# PID__v2.net
KiCad netlist of a schematic drawn in Altium Designer
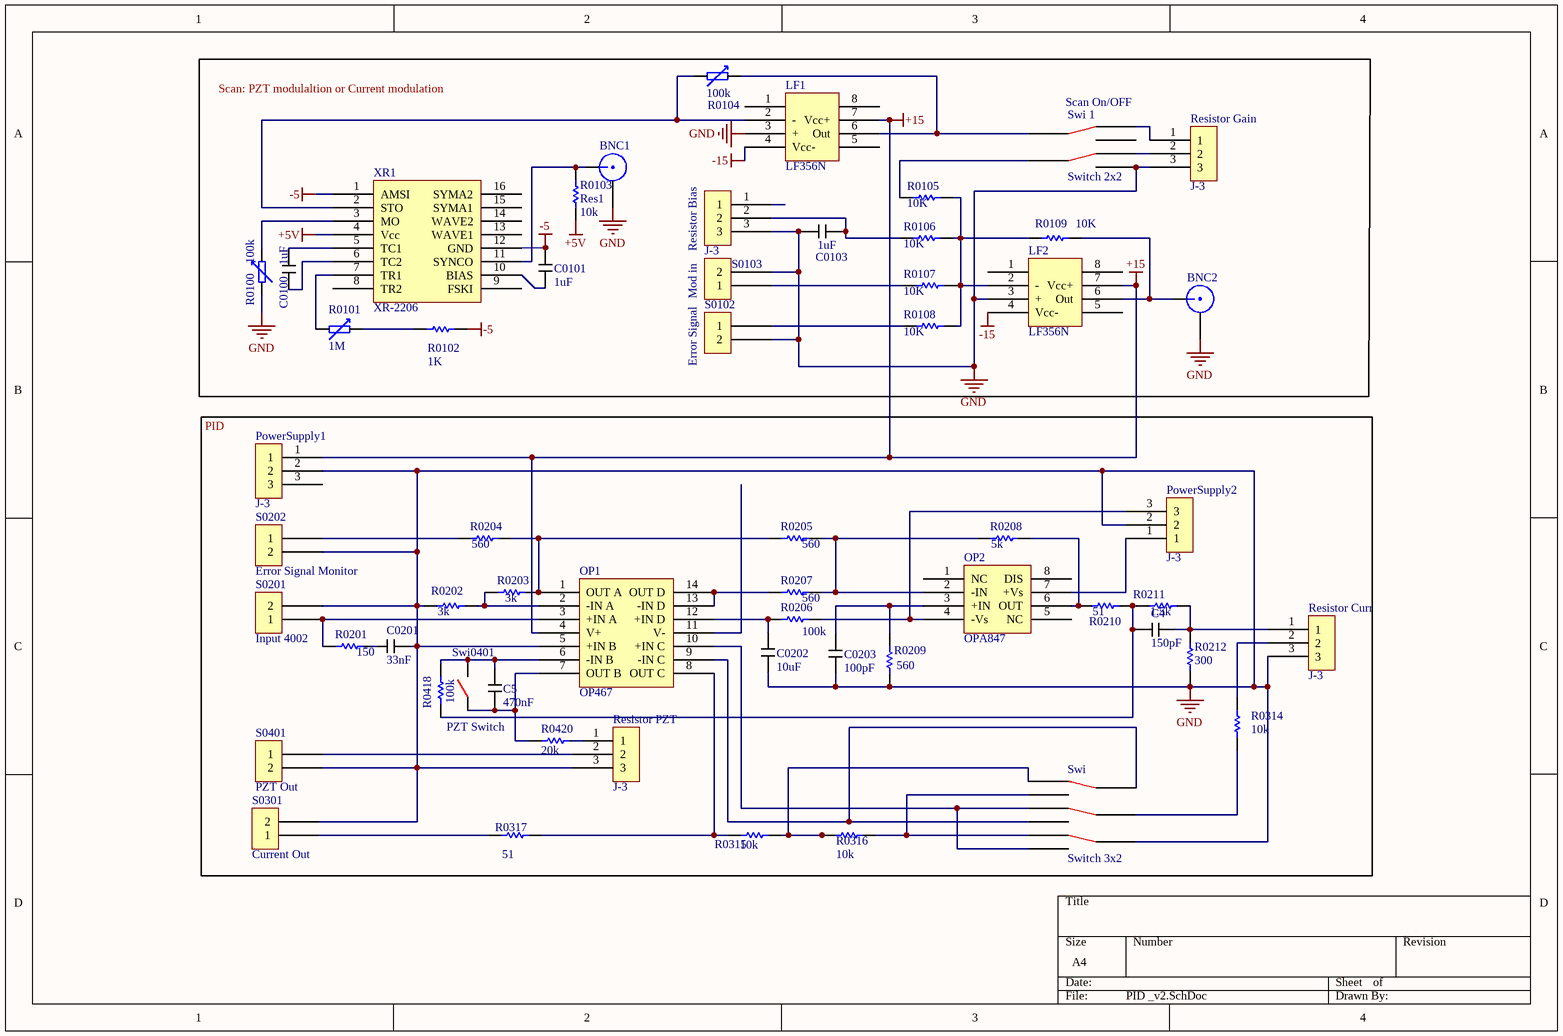
[diagram p0: PID _v2.SchDoc]

(export (version "E")
  (design (tool "Eeschema 10.0.6"))
  (components
    (comp (ref "BNC1") (value "BNC") (footprint "BNC-KE") (libsource (lib "Schlib1") (part "BNC")))
    (comp (ref "BNC2") (value "BNC") (footprint "BNC-KE") (libsource (lib "Schlib1") (part "BNC")))
    (comp (ref "C4") (value "150pF") (footprint "Capacitor") (libsource (lib "Schlib1") (part "Cap")))
    (comp (ref "C5") (value "470nF") (footprint "Capacitor") (libsource (lib "Schlib1") (part "Cap")))
    (comp (ref "C0100") (value "1uF") (footprint "Capacitor") (libsource (lib "Schlib1") (part "Cap")))
    (comp (ref "C0101") (value "1uF") (footprint "Capacitor") (libsource (lib "Schlib1") (part "Cap")))
    (comp (ref "C0103") (value "1uF") (footprint "Capacitor") (libsource (lib "Schlib1") (part "Cap")))
    (comp (ref "C0201") (value "33nF") (footprint "Capacitor") (libsource (lib "Schlib1") (part "Cap")))
    (comp (ref "C0202") (value "10uF") (footprint "Capacitor") (libsource (lib "Schlib1") (part "Cap")))
    (comp (ref "C0203") (value "100pF") (footprint "Capacitor") (libsource (lib "Schlib1") (part "Cap")))
    (comp (ref "LF1") (value "LF356N") (footprint "DIP8") (libsource (lib "Schlib1") (part "LF356N")))
    (comp (ref "LF2") (value "LF356N") (footprint "DIP8") (libsource (lib "Schlib1") (part "LF356N")))
    (comp (ref "OP1") (value "OP467") (footprint "DIP14") (libsource (lib "Schlib1") (part "OP467")))
    (comp (ref "OP2") (value "OPA847") (footprint "DIP8") (libsource (lib "Schlib1") (part "OPA847")))
    (comp (ref "PowerSupply1") (value "J-3") (footprint "J3") (libsource (lib "") (part "J-3_1")))
    (comp (ref "PowerSupply2") (value "J-3") (footprint "J3") (libsource (lib "") (part "J-3_2")))
    (comp (ref "R0100") (value "100k") (footprint "J3") (libsource (lib "Schlib1") (part "Res Adj")))
    (comp (ref "R0101") (value "1M") (footprint "J3") (libsource (lib "Schlib1") (part "Res Adj")))
    (comp (ref "R0102")
      (value "1K")
      (footprint "AXIAL-0.3")
      (description "Resistor")
      (fields (field (name "Comment") "Res1") (field (name "PUBLISHER") "Altium Limited"))
      (libsource (lib "Miscellaneous Devices") (part "Res1"))
    )
    (comp (ref "R0103")
      (value "Res1")
      (footprint "AXIAL-0.3")
      (description "Resistor")
      (fields (field (name "ALTIUM_VALUE") "10k") (field (name "PUBLISHER") "Altium Limited"))
      (libsource (lib "Miscellaneous Devices") (part "Res1"))
    )
    (comp (ref "R0104") (value "100k") (footprint "Res Adj 2") (libsource (lib "Schlib1") (part "Res Adj")))
    (comp (ref "R0105")
      (value "10K")
      (footprint "AXIAL-0.3")
      (description "Resistor")
      (fields (field (name "Comment") "Res1") (field (name "PUBLISHER") "Altium Limited"))
      (libsource (lib "Miscellaneous Devices") (part "Res1"))
    )
    (comp (ref "R0106")
      (value "10K")
      (footprint "AXIAL-0.3")
      (description "Resistor")
      (fields (field (name "Comment") "Res1") (field (name "PUBLISHER") "Altium Limited"))
      (libsource (lib "Miscellaneous Devices") (part "Res1"))
    )
    (comp (ref "R0107")
      (value "10K")
      (footprint "AXIAL-0.3")
      (description "Resistor")
      (fields (field (name "Comment") "Res1") (field (name "PUBLISHER") "Altium Limited"))
      (libsource (lib "Miscellaneous Devices") (part "Res1"))
    )
    (comp (ref "R0108")
      (value "10K")
      (footprint "AXIAL-0.3")
      (description "Resistor")
      (fields (field (name "Comment") "Res1") (field (name "PUBLISHER") "Altium Limited"))
      (libsource (lib "Miscellaneous Devices") (part "Res1"))
    )
    (comp (ref "R0109")
      (value "10K")
      (footprint "AXIAL-0.3")
      (description "Resistor")
      (fields (field (name "Comment") "Res1") (field (name "PUBLISHER") "Altium Limited"))
      (libsource (lib "Miscellaneous Devices") (part "Res1"))
    )
    (comp (ref "R0201")
      (value "150")
      (footprint "AXIAL-0.3")
      (description "Resistor")
      (fields (field (name "Comment") "Res1") (field (name "PUBLISHER") "Altium Limited"))
      (libsource (lib "Miscellaneous Devices") (part "Res1"))
    )
    (comp (ref "R0202")
      (value "3k")
      (footprint "AXIAL-0.3")
      (description "Resistor")
      (fields (field (name "Comment") "Res1") (field (name "PUBLISHER") "Altium Limited"))
      (libsource (lib "Miscellaneous Devices") (part "Res1"))
    )
    (comp (ref "R0203")
      (value "3k")
      (footprint "AXIAL-0.3")
      (description "Resistor")
      (fields (field (name "Comment") "Res1") (field (name "PUBLISHER") "Altium Limited"))
      (libsource (lib "Miscellaneous Devices") (part "Res1"))
    )
    (comp (ref "R0204")
      (value "560")
      (footprint "AXIAL-0.3")
      (description "Resistor")
      (fields (field (name "Comment") "Res1") (field (name "PUBLISHER") "Altium Limited"))
      (libsource (lib "Miscellaneous Devices") (part "Res1"))
    )
    (comp (ref "R0205")
      (value "560")
      (footprint "AXIAL-0.3")
      (description "Resistor")
      (fields (field (name "Comment") "Res1") (field (name "PUBLISHER") "Altium Limited"))
      (libsource (lib "Miscellaneous Devices") (part "Res1"))
    )
    (comp (ref "R0206")
      (value "100k")
      (footprint "AXIAL-0.3")
      (description "Resistor")
      (fields (field (name "Comment") "Res1") (field (name "PUBLISHER") "Altium Limited"))
      (libsource (lib "Miscellaneous Devices") (part "Res1"))
    )
    (comp (ref "R0207")
      (value "560")
      (footprint "AXIAL-0.3")
      (description "Resistor")
      (fields (field (name "Comment") "Res1") (field (name "PUBLISHER") "Altium Limited"))
      (libsource (lib "Miscellaneous Devices") (part "Res1"))
    )
    (comp (ref "R0208")
      (value "5k")
      (footprint "AXIAL-0.3")
      (description "Resistor")
      (fields (field (name "Comment") "Res1") (field (name "PUBLISHER") "Altium Limited"))
      (libsource (lib "Miscellaneous Devices") (part "Res1"))
    )
    (comp (ref "R0209")
      (value "560")
      (footprint "AXIAL-0.3")
      (description "Resistor")
      (fields (field (name "Comment") "Res1") (field (name "PUBLISHER") "Altium Limited"))
      (libsource (lib "Miscellaneous Devices") (part "Res1"))
    )
    (comp (ref "R0210")
      (value "51")
      (footprint "AXIAL-0.3")
      (description "Resistor")
      (fields (field (name "Comment") "Res1") (field (name "PUBLISHER") "Altium Limited"))
      (libsource (lib "Miscellaneous Devices") (part "Res1"))
    )
    (comp (ref "R0211")
      (value "1.5k")
      (footprint "AXIAL-0.3")
      (description "Resistor")
      (fields (field (name "Comment") "Res1") (field (name "PUBLISHER") "Altium Limited"))
      (libsource (lib "Miscellaneous Devices") (part "Res1"))
    )
    (comp (ref "R0212")
      (value "300")
      (footprint "AXIAL-0.3")
      (description "Resistor")
      (fields (field (name "Comment") "Res1") (field (name "PUBLISHER") "Altium Limited"))
      (libsource (lib "Miscellaneous Devices") (part "Res1"))
    )
    (comp (ref "R0314")
      (value "10k")
      (footprint "AXIAL-0.3")
      (description "Resistor")
      (fields (field (name "Comment") "Res1") (field (name "PUBLISHER") "Altium Limited"))
      (libsource (lib "Miscellaneous Devices") (part "Res1"))
    )
    (comp (ref "R0315")
      (value "10k")
      (footprint "AXIAL-0.3")
      (description "Resistor")
      (fields (field (name "Comment") "Res1") (field (name "PUBLISHER") "Altium Limited"))
      (libsource (lib "Miscellaneous Devices") (part "Res1"))
    )
    (comp (ref "R0316")
      (value "10k")
      (footprint "AXIAL-0.3")
      (description "Resistor")
      (fields (field (name "Comment") "Res1") (field (name "PUBLISHER") "Altium Limited"))
      (libsource (lib "Miscellaneous Devices") (part "Res1"))
    )
    (comp (ref "R0317")
      (value "51")
      (footprint "AXIAL-0.3")
      (description "Resistor")
      (fields (field (name "Comment") "Res1") (field (name "PUBLISHER") "Altium Limited"))
      (libsource (lib "Miscellaneous Devices") (part "Res1"))
    )
    (comp (ref "R0418")
      (value "100k")
      (footprint "AXIAL-0.3")
      (description "Resistor")
      (fields (field (name "Comment") "Res1") (field (name "PUBLISHER") "Altium Limited"))
      (libsource (lib "Miscellaneous Devices") (part "Res1"))
    )
    (comp (ref "R0420")
      (value "20k")
      (footprint "AXIAL-0.3")
      (description "Resistor")
      (fields (field (name "Comment") "Res1") (field (name "PUBLISHER") "Altium Limited"))
      (libsource (lib "Miscellaneous Devices") (part "Res1"))
    )
    (comp (ref "Resistor Bias") (value "J-3") (footprint "J3") (libsource (lib "") (part "J-3_1")))
    (comp (ref "Resistor Curr") (value "J-3") (footprint "J3") (libsource (lib "Schlib1") (part "J-3")))
    (comp (ref "Resistor Gain") (value "J-3") (footprint "J3") (libsource (lib "Schlib1") (part "J-3")))
    (comp (ref "Resistor PZT") (value "J-3") (footprint "J3") (libsource (lib "Schlib1") (part "J-3")))
    (comp (ref "S0102") (value "Error Signal") (footprint "SMA-S") (libsource (lib "") (part "SMA-S_1")))
    (comp (ref "S0103") (value "Mod in") (footprint "SMA-S") (libsource (lib "Schlib1") (part "SMA-S")))
    (comp (ref "S0201") (value "Input 4002") (footprint "SMA-S") (libsource (lib "Schlib1") (part "SMA-S")))
    (comp (ref "S0202")
      (value "Error Signal Monitor")
      (footprint "SMA-S")
      (libsource (lib "") (part "SMA-S_1"))
    )
    (comp (ref "S0301") (value "Current Out") (footprint "SMA-S") (libsource (lib "Schlib1") (part "SMA-S")))
    (comp (ref "S0401") (value "PZT Out") (footprint "SMA-S") (libsource (lib "") (part "SMA-S_1")))
    (comp (ref "Swi")
      (value "Switch 3x2")
      (footprint "Swi 3x2")
      (libsource (lib "Schlib1") (part "Switch 3x2"))
    )
    (comp (ref "Swi 1")
      (value "Switch 2x2")
      (footprint "Swi 2x2")
      (libsource (lib "Schlib1") (part "Switch 2x2"))
    )
    (comp (ref "Swi0401")
      (value "PZT Switch")
      (footprint "J2")
      (libsource (lib "Schlib1") (part "Switch 1x1"))
    )
    (comp (ref "XR1") (value "XR-2206") (footprint "DIP16") (libsource (lib "Schlib1") (part "XR-2206")))
  )
  (nets
    (net (code "1") (name "+5V") (class "Default")
      (node (ref "R0103") (pin "1") (pinfunction "1_1") (pintype "passive"))
      (node (ref "XR1") (pin "4") (pinfunction "Vcc_4") (pintype "passive"))
    )
    (net (code "2") (name "+15") (class "Default")
      (node (ref "LF1") (pin "7") (pinfunction "Vcc+_7") (pintype "passive"))
      (node (ref "LF2") (pin "7") (pinfunction "Vcc+_7") (pintype "passive"))
      (node (ref "OP1") (pin "4") (pinfunction "V+_4") (pintype "passive"))
      (node (ref "PowerSupply1") (pin "1") (pinfunction "1_1") (pintype "passive"))
    )
    (net (code "3") (name "-5") (class "Default")
      (node (ref "C0101") (pin "2") (pinfunction "2_2") (pintype "passive"))
      (node (ref "R0102") (pin "2") (pinfunction "2_2") (pintype "passive"))
      (node (ref "XR1") (pin "1") (pinfunction "AMSI_1") (pintype "passive"))
      (node (ref "XR1") (pin "12") (pinfunction "GND_12") (pintype "passive"))
    )
    (net (code "4") (name "-15") (class "Default")
      (node (ref "LF1") (pin "4") (pinfunction "Vcc-_4") (pintype "passive"))
      (node (ref "LF2") (pin "4") (pinfunction "Vcc-_4") (pintype "passive"))
    )
    (net (code "5") (name "GND") (class "Default")
      (node (ref "BNC1") (pin "2") (pinfunction "2_2") (pintype "passive"))
      (node (ref "BNC2") (pin "2") (pinfunction "2_2") (pintype "passive"))
      (node (ref "C0103") (pin "1") (pinfunction "1_1") (pintype "passive"))
      (node (ref "C0201") (pin "2") (pinfunction "2_2") (pintype "passive"))
      (node (ref "C0202") (pin "1") (pinfunction "1_1") (pintype "passive"))
      (node (ref "C0203") (pin "2") (pinfunction "2_2") (pintype "passive"))
      (node (ref "LF1") (pin "3") (pinfunction "+_3") (pintype "passive"))
      (node (ref "LF2") (pin "3") (pinfunction "+_3") (pintype "passive"))
      (node (ref "OP1") (pin "5") (pinfunction "+IN_B_5") (pintype "passive"))
      (node (ref "PowerSupply1") (pin "2") (pinfunction "2_2") (pintype "passive"))
      (node (ref "PowerSupply2") (pin "2") (pinfunction "2_2") (pintype "passive"))
      (node (ref "R0100") (pin "1") (pinfunction "1_1") (pintype "passive"))
      (node (ref "R0202") (pin "2") (pinfunction "2_2") (pintype "passive"))
      (node (ref "R0209") (pin "1") (pinfunction "1_1") (pintype "passive"))
      (node (ref "R0212") (pin "2") (pinfunction "2_2") (pintype "passive"))
      (node (ref "Resistor Bias") (pin "3") (pinfunction "3_3") (pintype "passive"))
      (node (ref "Resistor Curr") (pin "3") (pinfunction "3_3") (pintype "passive"))
      (node (ref "Resistor Gain") (pin "3") (pinfunction "3_3") (pintype "passive"))
      (node (ref "Resistor PZT") (pin "3") (pinfunction "3_3") (pintype "passive"))
      (node (ref "S0102") (pin "2") (pinfunction "2_2") (pintype "passive"))
      (node (ref "S0103") (pin "2") (pinfunction "2_2") (pintype "passive"))
      (node (ref "S0201") (pin "2") (pinfunction "2_2") (pintype "passive"))
      (node (ref "S0202") (pin "2") (pinfunction "2_2") (pintype "passive"))
      (node (ref "S0301") (pin "2") (pinfunction "2_2") (pintype "passive"))
      (node (ref "S0401") (pin "2") (pinfunction "2_2") (pintype "passive"))
      (node (ref "Swi") (pin "3") (pinfunction "3_3") (pintype "passive"))
      (node (ref "Swi 1") (pin "6") (pinfunction "6_6") (pintype "passive"))
    )
    (net (code "6") (name "Net-(C4-Pad1)") (class "Default")
      (node (ref "C4") (pin "1") (pinfunction "1_1") (pintype "passive"))
      (node (ref "R0211") (pin "2") (pinfunction "2_2") (pintype "passive"))
      (node (ref "R0212") (pin "1") (pinfunction "1_1") (pintype "passive"))
      (node (ref "Resistor Curr") (pin "1") (pinfunction "1_1") (pintype "passive"))
    )
    (net (code "7") (name "Net-(C4-Pad2)") (class "Default")
      (node (ref "C4") (pin "2") (pinfunction "2_2") (pintype "passive"))
      (node (ref "R0210") (pin "2") (pinfunction "2_2") (pintype "passive"))
      (node (ref "R0211") (pin "1") (pinfunction "1_1") (pintype "passive"))
      (node (ref "R0418") (pin "1") (pinfunction "1_1") (pintype "passive"))
    )
    (net (code "8") (name "Net-(C0103-Pad2)") (class "Default")
      (node (ref "C0103") (pin "2") (pinfunction "2_2") (pintype "passive"))
      (node (ref "R0106") (pin "1") (pinfunction "1_1") (pintype "passive"))
      (node (ref "Resistor Bias") (pin "2") (pinfunction "2_2") (pintype "passive"))
    )
    (net (code "9") (name "Net-(C0201-Pad1)") (class "Default")
      (node (ref "C0201") (pin "1") (pinfunction "1_1") (pintype "passive"))
      (node (ref "R0201") (pin "2") (pinfunction "2_2") (pintype "passive"))
    )
    (net (code "10") (name "Net-(LF1--)") (class "Default")
      (node (ref "LF1") (pin "2") (pinfunction "-_2") (pintype "passive"))
      (node (ref "R0104") (pin "1") (pinfunction "1_1") (pintype "passive"))
      (node (ref "XR1") (pin "2") (pinfunction "STO_2") (pintype "passive"))
    )
    (net (code "11") (name "Net-(LF1-Out)") (class "Default")
      (node (ref "LF1") (pin "6") (pinfunction "Out_6") (pintype "passive"))
      (node (ref "R0104") (pin "2") (pinfunction "2_2") (pintype "passive"))
      (node (ref "Swi 1") (pin "1") (pinfunction "1_1") (pintype "passive"))
    )
    (net (code "12") (name "Net-(LF2--)") (class "Default")
      (node (ref "LF2") (pin "2") (pinfunction "-_2") (pintype "passive"))
      (node (ref "R0105") (pin "2") (pinfunction "2_2") (pintype "passive"))
      (node (ref "R0106") (pin "2") (pinfunction "2_2") (pintype "passive"))
      (node (ref "R0107") (pin "2") (pinfunction "2_2") (pintype "passive"))
      (node (ref "R0108") (pin "2") (pinfunction "2_2") (pintype "passive"))
      (node (ref "R0109") (pin "1") (pinfunction "1_1") (pintype "passive"))
    )
    (net (code "13") (name "Net-(LF2-Out)") (class "Default")
      (node (ref "BNC2") (pin "1") (pinfunction "1_1") (pintype "passive"))
      (node (ref "LF2") (pin "6") (pinfunction "Out_6") (pintype "passive"))
      (node (ref "R0109") (pin "2") (pinfunction "2_2") (pintype "passive"))
    )
    (net (code "14") (name "Net-(OP1-+IN_A)") (class "Default")
      (node (ref "OP1") (pin "3") (pinfunction "+IN_A_3") (pintype "passive"))
      (node (ref "R0201") (pin "1") (pinfunction "1_1") (pintype "passive"))
      (node (ref "S0201") (pin "1") (pinfunction "1_1") (pintype "passive"))
    )
    (net (code "15") (name "Net-(OP1-+IN_C)") (class "Default")
      (node (ref "OP1") (pin "10") (pinfunction "+IN_C_10") (pintype "passive"))
      (node (ref "Swi") (pin "6") (pinfunction "6_6") (pintype "passive"))
      (node (ref "Swi") (pin "9") (pinfunction "9_9") (pintype "passive"))
    )
    (net (code "16") (name "Net-(OP1-+IN_D)") (class "Default")
      (node (ref "C0202") (pin "2") (pinfunction "2_2") (pintype "passive"))
      (node (ref "OP1") (pin "12") (pinfunction "+IN_D_12") (pintype "passive"))
      (node (ref "R0206") (pin "2") (pinfunction "2_2") (pintype "passive"))
    )
    (net (code "17") (name "Net-(OP1--IN_A)") (class "Default")
      (node (ref "OP1") (pin "2") (pinfunction "-IN_A_2") (pintype "passive"))
      (node (ref "R0202") (pin "1") (pinfunction "1_1") (pintype "passive"))
      (node (ref "R0203") (pin "1") (pinfunction "1_1") (pintype "passive"))
    )
    (net (code "18") (name "Net-(OP1--IN_B)") (class "Default")
      (node (ref "C5") (pin "1") (pinfunction "1_1") (pintype "passive"))
      (node (ref "OP1") (pin "6") (pinfunction "-IN_B_6") (pintype "passive"))
      (node (ref "R0418") (pin "2") (pinfunction "2_2") (pintype "passive"))
      (node (ref "Swi0401") (pin "2") (pinfunction "2_2") (pintype "passive"))
    )
    (net (code "19") (name "Net-(OP1--IN_C)") (class "Default")
      (node (ref "OP1") (pin "9") (pinfunction "-IN_C_9") (pintype "passive"))
      (node (ref "Swi") (pin "1") (pinfunction "1_1") (pintype "passive"))
      (node (ref "Swi") (pin "7") (pinfunction "7_7") (pintype "passive"))
    )
    (net (code "20") (name "Net-(OP1--IN_D)") (class "Default")
      (node (ref "OP1") (pin "13") (pinfunction "-IN_D_13") (pintype "passive"))
      (node (ref "OP1") (pin "14") (pinfunction "OUT_D_14") (pintype "passive"))
      (node (ref "R0207") (pin "1") (pinfunction "1_1") (pintype "passive"))
    )
    (net (code "21") (name "Net-(OP1-OUT_A)") (class "Default")
      (node (ref "OP1") (pin "1") (pinfunction "OUT_A_1") (pintype "passive"))
      (node (ref "R0203") (pin "2") (pinfunction "2_2") (pintype "passive"))
      (node (ref "R0204") (pin "2") (pinfunction "2_2") (pintype "passive"))
      (node (ref "R0205") (pin "1") (pinfunction "1_1") (pintype "passive"))
    )
    (net (code "22") (name "Net-(OP1-OUT_B)") (class "Default")
      (node (ref "C5") (pin "2") (pinfunction "2_2") (pintype "passive"))
      (node (ref "OP1") (pin "7") (pinfunction "OUT_B_7") (pintype "passive"))
      (node (ref "R0420") (pin "2") (pinfunction "2_2") (pintype "passive"))
      (node (ref "Swi0401") (pin "1") (pinfunction "1_1") (pintype "passive"))
    )
    (net (code "23") (name "Net-(OP1-OUT_C)") (class "Default")
      (node (ref "OP1") (pin "8") (pinfunction "OUT_C_8") (pintype "passive"))
      (node (ref "R0315") (pin "2") (pinfunction "2_2") (pintype "passive"))
      (node (ref "R0317") (pin "2") (pinfunction "2_2") (pintype "passive"))
    )
    (net (code "24") (name "Net-(OP2-+IN)") (class "Default")
      (node (ref "C0203") (pin "1") (pinfunction "1_1") (pintype "passive"))
      (node (ref "OP2") (pin "3") (pinfunction "+IN_3") (pintype "passive"))
      (node (ref "R0209") (pin "2") (pinfunction "2_2") (pintype "passive"))
    )
    (net (code "25") (name "Net-(OP2-+Vs)") (class "Default")
      (node (ref "OP2") (pin "7") (pinfunction "+Vs_7") (pintype "passive"))
      (node (ref "PowerSupply2") (pin "1") (pinfunction "1_1") (pintype "passive"))
    )
    (net (code "26") (name "Net-(OP2--IN)") (class "Default")
      (node (ref "OP2") (pin "2") (pinfunction "-IN_2") (pintype "passive"))
      (node (ref "R0205") (pin "2") (pinfunction "2_2") (pintype "passive"))
      (node (ref "R0207") (pin "2") (pinfunction "2_2") (pintype "passive"))
      (node (ref "R0208") (pin "1") (pinfunction "1_1") (pintype "passive"))
    )
    (net (code "27") (name "Net-(OP2--Vs)") (class "Default")
      (node (ref "OP2") (pin "4") (pinfunction "-Vs_4") (pintype "passive"))
      (node (ref "PowerSupply2") (pin "3") (pinfunction "3_3") (pintype "passive"))
      (node (ref "R0206") (pin "1") (pinfunction "1_1") (pintype "passive"))
    )
    (net (code "28") (name "Net-(OP2-OUT)") (class "Default")
      (node (ref "OP2") (pin "6") (pinfunction "OUT_6") (pintype "passive"))
      (node (ref "R0208") (pin "2") (pinfunction "2_2") (pintype "passive"))
      (node (ref "R0210") (pin "1") (pinfunction "1_1") (pintype "passive"))
    )
    (net (code "29") (name "Net-(R0101-Pad2)") (class "Default")
      (node (ref "R0101") (pin "2") (pinfunction "2_2") (pintype "passive"))
      (node (ref "R0102") (pin "1") (pinfunction "1_1") (pintype "passive"))
    )
    (net (code "30") (name "Net-(R0105-Pad1)") (class "Default")
      (node (ref "R0105") (pin "1") (pinfunction "1_1") (pintype "passive"))
      (node (ref "Swi 1") (pin "2") (pinfunction "2_2") (pintype "passive"))
    )
    (net (code "31") (name "Net-(R0107-Pad1)") (class "Default")
      (node (ref "R0107") (pin "1") (pinfunction "1_1") (pintype "passive"))
      (node (ref "S0103") (pin "1") (pinfunction "1_1") (pintype "passive"))
    )
    (net (code "32") (name "Net-(R0108-Pad1)") (class "Default")
      (node (ref "R0108") (pin "1") (pinfunction "1_1") (pintype "passive"))
      (node (ref "S0102") (pin "1") (pinfunction "1_1") (pintype "passive"))
    )
    (net (code "33") (name "Net-(R0204-Pad1)") (class "Default")
      (node (ref "R0204") (pin "1") (pinfunction "1_1") (pintype "passive"))
      (node (ref "S0202") (pin "1") (pinfunction "1_1") (pintype "passive"))
    )
    (net (code "34") (name "Net-(R0314-Pad1)") (class "Default")
      (node (ref "R0314") (pin "1") (pinfunction "1_1") (pintype "passive"))
      (node (ref "Swi") (pin "2") (pinfunction "2_2") (pintype "passive"))
    )
    (net (code "35") (name "Net-(R0314-Pad2)") (class "Default")
      (node (ref "R0314") (pin "2") (pinfunction "2_2") (pintype "passive"))
      (node (ref "Resistor Curr") (pin "2") (pinfunction "2_2") (pintype "passive"))
    )
    (net (code "36") (name "Net-(R0315-Pad1)") (class "Default")
      (node (ref "R0315") (pin "1") (pinfunction "1_1") (pintype "passive"))
      (node (ref "R0316") (pin "2") (pinfunction "2_2") (pintype "passive"))
      (node (ref "Swi") (pin "4") (pinfunction "4_4") (pintype "passive"))
    )
    (net (code "37") (name "Net-(R0316-Pad1)") (class "Default")
      (node (ref "R0316") (pin "1") (pinfunction "1_1") (pintype "passive"))
      (node (ref "Swi") (pin "5") (pinfunction "5_5") (pintype "passive"))
      (node (ref "Swi") (pin "8") (pinfunction "8_8") (pintype "passive"))
    )
    (net (code "38") (name "Net-(R0317-Pad1)") (class "Default")
      (node (ref "R0317") (pin "1") (pinfunction "1_1") (pintype "passive"))
      (node (ref "S0301") (pin "1") (pinfunction "1_1") (pintype "passive"))
    )
    (net (code "39") (name "Net-(R0420-Pad1)") (class "Default")
      (node (ref "R0420") (pin "1") (pinfunction "1_1") (pintype "passive"))
      (node (ref "Resistor PZT") (pin "1") (pinfunction "1_1") (pintype "passive"))
    )
    (net (code "40") (name "Net-(Resistor Gain-Pad1)") (class "Default")
      (node (ref "Resistor Gain") (pin "1") (pinfunction "1_1") (pintype "passive"))
      (node (ref "Swi 1") (pin "3") (pinfunction "3_3") (pintype "passive"))
    )
    (net (code "41") (name "Net-(Resistor Gain-Pad2)") (class "Default")
      (node (ref "Resistor Gain") (pin "2") (pinfunction "2_2") (pintype "passive"))
      (node (ref "Swi 1") (pin "4") (pinfunction "4_4") (pintype "passive"))
    )
    (net (code "42") (name "Net-(Resistor PZT-Pad2)") (class "Default")
      (node (ref "Resistor PZT") (pin "2") (pinfunction "2_2") (pintype "passive"))
      (node (ref "S0401") (pin "1") (pinfunction "1_1") (pintype "passive"))
    )
    (net (code "43") (name "Net-(XR1-BIAS)") (class "Default")
      (node (ref "C0101") (pin "1") (pinfunction "1_1") (pintype "passive"))
      (node (ref "XR1") (pin "10") (pinfunction "BIAS_10") (pintype "passive"))
    )
    (net (code "44") (name "Net-(XR1-MO)") (class "Default")
      (node (ref "R0100") (pin "2") (pinfunction "2_2") (pintype "passive"))
      (node (ref "XR1") (pin "3") (pinfunction "MO_3") (pintype "passive"))
    )
    (net (code "45") (name "Net-(XR1-SYNCO)") (class "Default")
      (node (ref "BNC1") (pin "1") (pinfunction "1_1") (pintype "passive"))
      (node (ref "R0103") (pin "2") (pinfunction "2_2") (pintype "passive"))
      (node (ref "XR1") (pin "11") (pinfunction "SYNCO_11") (pintype "passive"))
    )
    (net (code "46") (name "Net-(XR1-TC1)") (class "Default")
      (node (ref "C0100") (pin "1") (pinfunction "1_1") (pintype "passive"))
      (node (ref "XR1") (pin "5") (pinfunction "TC1_5") (pintype "passive"))
    )
    (net (code "47") (name "Net-(XR1-TC2)") (class "Default")
      (node (ref "C0100") (pin "2") (pinfunction "2_2") (pintype "passive"))
      (node (ref "XR1") (pin "6") (pinfunction "TC2_6") (pintype "passive"))
    )
    (net (code "48") (name "Net-(XR1-TR1)") (class "Default")
      (node (ref "R0101") (pin "1") (pinfunction "1_1") (pintype "passive"))
      (node (ref "XR1") (pin "7") (pinfunction "TR1_7") (pintype "passive"))
    )
    (net (code "49") (name "unconnected-(LF1-N.C.-Pad8)") (class "Default")
      (node (ref "LF1") (pin "8") (pinfunction "N.C._8") (pintype "passive"))
    )
    (net (code "50") (name "unconnected-(LF1-Offset_Null-Pad1)") (class "Default")
      (node (ref "LF1") (pin "1") (pinfunction "Offset_Null_1") (pintype "passive"))
    )
    (net (code "51") (name "unconnected-(LF1-Offset_Null2-Pad5)") (class "Default")
      (node (ref "LF1") (pin "5") (pinfunction "Offset_Null2_5") (pintype "passive"))
    )
    (net (code "52") (name "unconnected-(LF2-N.C.-Pad8)") (class "Default")
      (node (ref "LF2") (pin "8") (pinfunction "N.C._8") (pintype "passive"))
    )
    (net (code "53") (name "unconnected-(LF2-Offset_Null-Pad1)") (class "Default")
      (node (ref "LF2") (pin "1") (pinfunction "Offset_Null_1") (pintype "passive"))
    )
    (net (code "54") (name "unconnected-(LF2-Offset_Null2-Pad5)") (class "Default")
      (node (ref "LF2") (pin "5") (pinfunction "Offset_Null2_5") (pintype "passive"))
    )
    (net (code "55") (name "unconnected-(OP1-V--Pad11)") (class "Default")
      (node (ref "OP1") (pin "11") (pinfunction "V-_11") (pintype "passive"))
    )
    (net (code "56") (name "unconnected-(OP2-DIS-Pad8)") (class "Default")
      (node (ref "OP2") (pin "8") (pinfunction "DIS_8") (pintype "passive"))
    )
    (net (code "57") (name "unconnected-(OP2-NC-Pad1)") (class "Default")
      (node (ref "OP2") (pin "1") (pinfunction "NC_1") (pintype "passive"))
    )
    (net (code "58") (name "unconnected-(OP2-NC-Pad5)") (class "Default")
      (node (ref "OP2") (pin "5") (pinfunction "NC_5") (pintype "passive"))
    )
    (net (code "59") (name "unconnected-(PowerSupply1-Pad3)") (class "Default")
      (node (ref "PowerSupply1") (pin "3") (pinfunction "3_3") (pintype "passive"))
    )
    (net (code "60") (name "unconnected-(Resistor Bias-Pad1)") (class "Default")
      (node (ref "Resistor Bias") (pin "1") (pinfunction "1_1") (pintype "passive"))
    )
    (net (code "61") (name "unconnected-(Swi 1-Pad5)") (class "Default")
      (node (ref "Swi 1") (pin "5") (pinfunction "5_5") (pintype "passive"))
    )
    (net (code "62") (name "unconnected-(XR1-FSKI-Pad9)") (class "Default")
      (node (ref "XR1") (pin "9") (pinfunction "FSKI_9") (pintype "passive"))
    )
    (net (code "63") (name "unconnected-(XR1-SYMA1-Pad15)") (class "Default")
      (node (ref "XR1") (pin "15") (pinfunction "SYMA1_15") (pintype "passive"))
    )
    (net (code "64") (name "unconnected-(XR1-SYMA2-Pad16)") (class "Default")
      (node (ref "XR1") (pin "16") (pinfunction "SYMA2_16") (pintype "passive"))
    )
    (net (code "65") (name "unconnected-(XR1-TR2-Pad8)") (class "Default")
      (node (ref "XR1") (pin "8") (pinfunction "TR2_8") (pintype "passive"))
    )
    (net (code "66") (name "unconnected-(XR1-WAVE1-Pad13)") (class "Default")
      (node (ref "XR1") (pin "13") (pinfunction "WAVE1_13") (pintype "passive"))
    )
    (net (code "67") (name "unconnected-(XR1-WAVE2-Pad14)") (class "Default")
      (node (ref "XR1") (pin "14") (pinfunction "WAVE2_14") (pintype "passive"))
    )
  )
)
